# IV9_Christmas.net
KiCad netlist of a schematic drawn in EAGLE
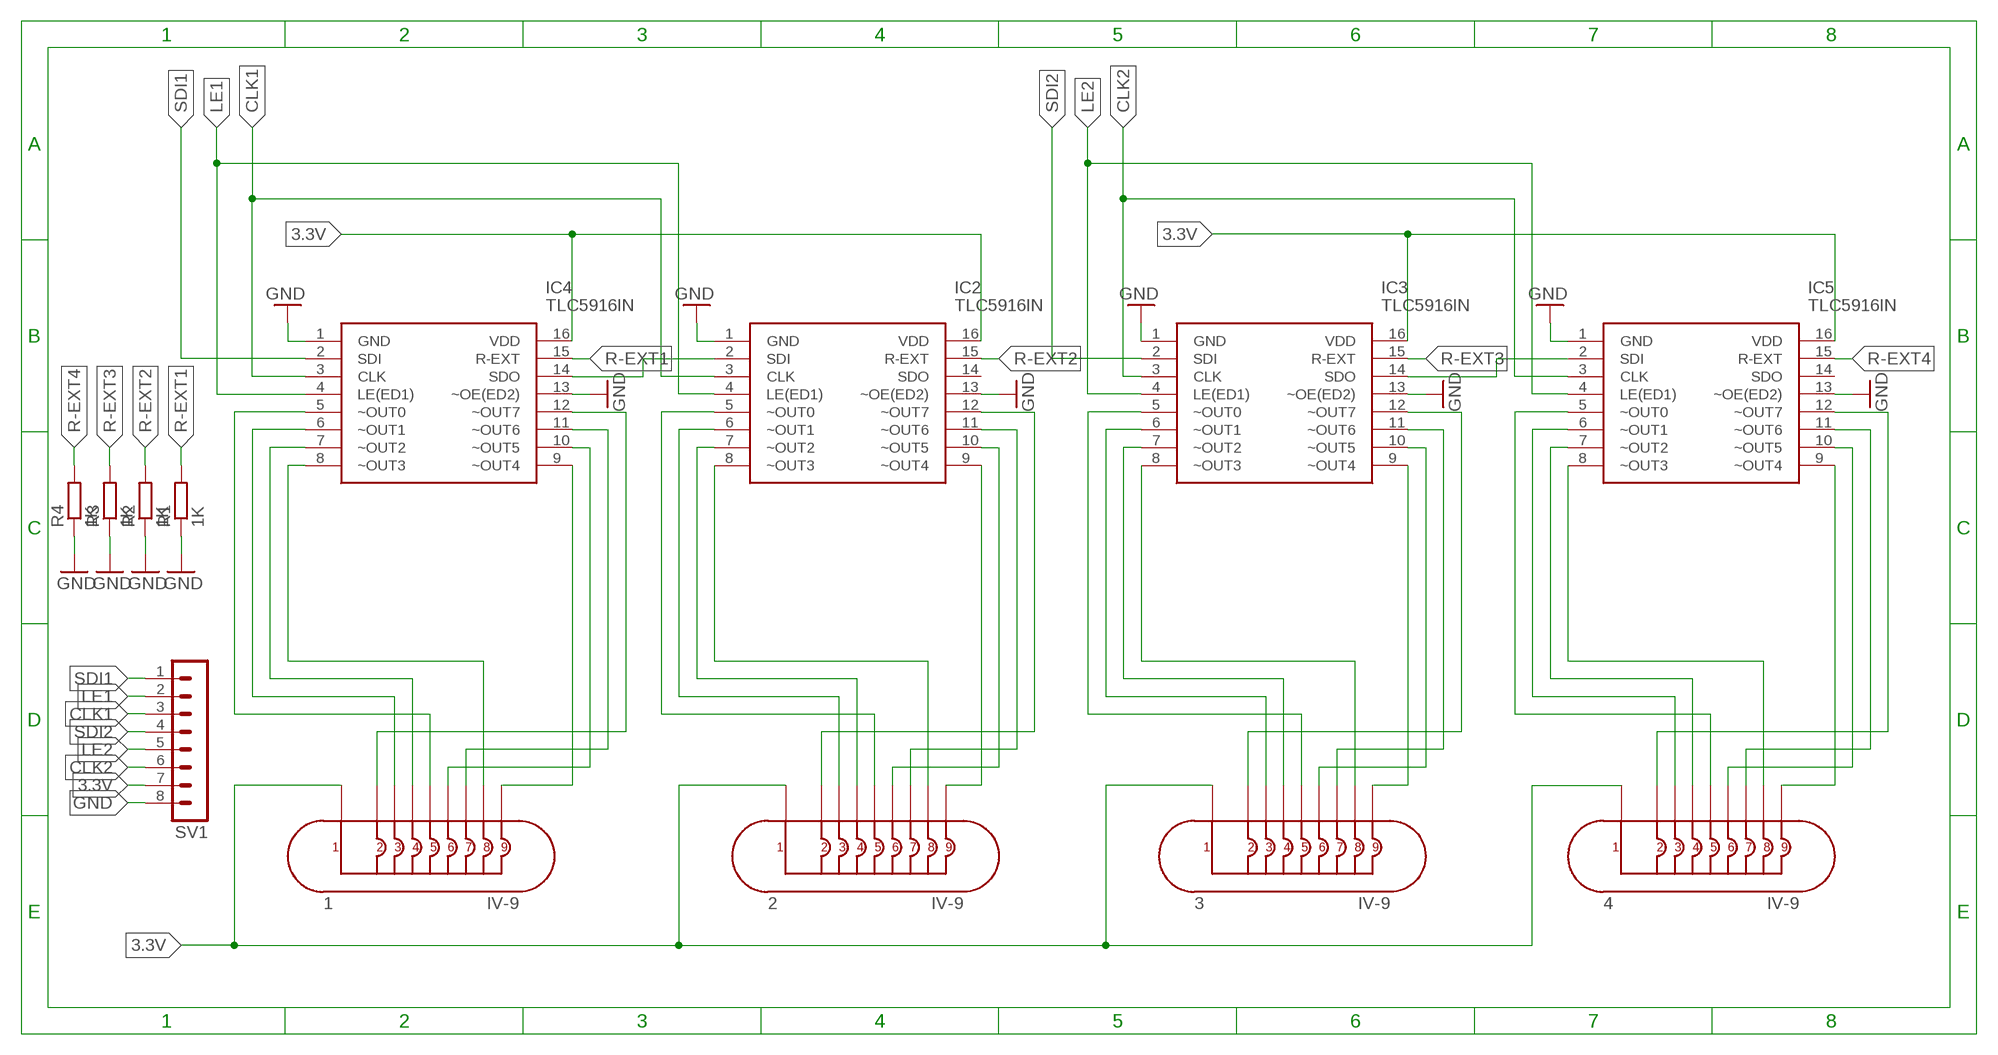
[diagram p0: schematic, sheet 1]
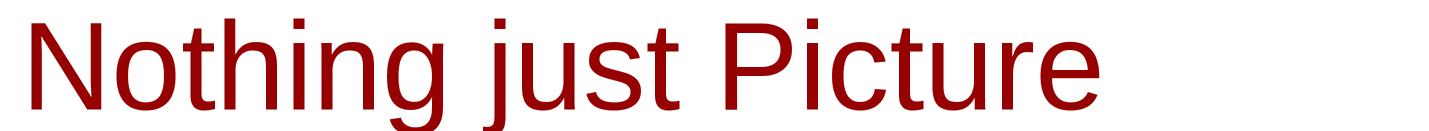
[diagram p1: schematic, sheet 2]

(export (version "E")
  (design (tool "Eeschema 10.0.6"))
  (components
    (comp (ref "1")
      (value "IV-9")
      (footprint "eagle-import:IV-9")
      (libsource (lib "eagle-import") (part "IV-9"))
    )
    (comp (ref "2")
      (value "IV-9")
      (footprint "eagle-import:IV-9")
      (libsource (lib "eagle-import") (part "IV-9"))
    )
    (comp (ref "3")
      (value "IV-9")
      (footprint "eagle-import:IV-9")
      (libsource (lib "eagle-import") (part "IV-9"))
    )
    (comp (ref "4")
      (value "IV-9")
      (footprint "eagle-import:IV-9")
      (libsource (lib "eagle-import") (part "IV-9"))
    )
    (comp (ref "IC2")
      (value "TLC5916IN")
      (footprint "eagle-import:DIP254P762X508-16")
      (fields (field (name "MOUSER_PART_NUMBER") "595-TLC5916IN"))
      (libsource (lib "eagle-import") (part "TLC5916IN"))
    )
    (comp (ref "IC3")
      (value "TLC5916IN")
      (footprint "eagle-import:DIP254P762X508-16")
      (fields (field (name "MOUSER_PART_NUMBER") "595-TLC5916IN"))
      (libsource (lib "eagle-import") (part "TLC5916IN"))
    )
    (comp (ref "IC4")
      (value "TLC5916IN")
      (footprint "eagle-import:DIP254P762X508-16")
      (fields (field (name "MOUSER_PART_NUMBER") "595-TLC5916IN"))
      (libsource (lib "eagle-import") (part "TLC5916IN"))
    )
    (comp (ref "IC5")
      (value "TLC5916IN")
      (footprint "eagle-import:DIP254P762X508-16")
      (fields (field (name "MOUSER_PART_NUMBER") "595-TLC5916IN"))
      (libsource (lib "eagle-import") (part "TLC5916IN"))
    )
    (comp (ref "R1")
      (value "1K")
      (footprint "eagle-import:R1206")
      (libsource (lib "eagle-import") (part "R-EU_R1206"))
    )
    (comp (ref "R2")
      (value "1K")
      (footprint "eagle-import:R1206")
      (libsource (lib "eagle-import") (part "R-EU_R1206"))
    )
    (comp (ref "R3")
      (value "1K")
      (footprint "eagle-import:R1206")
      (libsource (lib "eagle-import") (part "R-EU_R1206"))
    )
    (comp (ref "R4")
      (value "1K")
      (footprint "eagle-import:R1206")
      (libsource (lib "eagle-import") (part "R-EU_R1206"))
    )
    (comp (ref "SV1")
      (value "MA08-1")
      (footprint "eagle-import:MA08-1")
      (libsource (lib "eagle-import") (part "MA08-1"))
    )
  )
  (nets
    (net (code "1") (name "3.3V") (class "Default")
      (node (ref "1") (pin "1") (pinfunction "1_1") (pintype "bidirectional"))
      (node (ref "2") (pin "1") (pinfunction "1_1") (pintype "bidirectional"))
      (node (ref "3") (pin "1") (pinfunction "1_1") (pintype "bidirectional"))
      (node (ref "4") (pin "1") (pinfunction "1_1") (pintype "bidirectional"))
      (node (ref "IC2") (pin "16") (pinfunction "VDD_16") (pintype "bidirectional"))
      (node (ref "IC3") (pin "16") (pinfunction "VDD_16") (pintype "bidirectional"))
      (node (ref "IC4") (pin "16") (pinfunction "VDD_16") (pintype "bidirectional"))
      (node (ref "IC5") (pin "16") (pinfunction "VDD_16") (pintype "bidirectional"))
      (node (ref "SV1") (pin "7") (pinfunction "7_7") (pintype "passive"))
    )
    (net (code "2") (name "CLK1") (class "Default")
      (node (ref "IC2") (pin "3") (pinfunction "CLK_3") (pintype "bidirectional"))
      (node (ref "IC4") (pin "3") (pinfunction "CLK_3") (pintype "bidirectional"))
      (node (ref "SV1") (pin "3") (pinfunction "3_3") (pintype "passive"))
    )
    (net (code "3") (name "CLK2") (class "Default")
      (node (ref "IC3") (pin "3") (pinfunction "CLK_3") (pintype "bidirectional"))
      (node (ref "IC5") (pin "3") (pinfunction "CLK_3") (pintype "bidirectional"))
      (node (ref "SV1") (pin "6") (pinfunction "6_6") (pintype "passive"))
    )
    (net (code "4") (name "GND") (class "Default")
      (node (ref "IC2") (pin "1") (pinfunction "GND_1") (pintype "bidirectional"))
      (node (ref "IC2") (pin "13") (pinfunction "~{OE(ED2})_13") (pintype "bidirectional"))
      (node (ref "IC3") (pin "1") (pinfunction "GND_1") (pintype "bidirectional"))
      (node (ref "IC3") (pin "13") (pinfunction "~{OE(ED2})_13") (pintype "bidirectional"))
      (node (ref "IC4") (pin "1") (pinfunction "GND_1") (pintype "bidirectional"))
      (node (ref "IC4") (pin "13") (pinfunction "~{OE(ED2})_13") (pintype "bidirectional"))
      (node (ref "IC5") (pin "1") (pinfunction "GND_1") (pintype "bidirectional"))
      (node (ref "IC5") (pin "13") (pinfunction "~{OE(ED2})_13") (pintype "bidirectional"))
      (node (ref "R1") (pin "1") (pinfunction "1_1") (pintype "passive"))
      (node (ref "R2") (pin "1") (pinfunction "1_1") (pintype "passive"))
      (node (ref "R3") (pin "1") (pinfunction "1_1") (pintype "passive"))
      (node (ref "R4") (pin "1") (pinfunction "1_1") (pintype "passive"))
      (node (ref "SV1") (pin "8") (pinfunction "8_8") (pintype "passive"))
    )
    (net (code "5") (name "LE1") (class "Default")
      (node (ref "IC2") (pin "4") (pinfunction "LE(ED1)_4") (pintype "bidirectional"))
      (node (ref "IC4") (pin "4") (pinfunction "LE(ED1)_4") (pintype "bidirectional"))
      (node (ref "SV1") (pin "2") (pinfunction "2_2") (pintype "passive"))
    )
    (net (code "6") (name "LE2") (class "Default")
      (node (ref "IC3") (pin "4") (pinfunction "LE(ED1)_4") (pintype "bidirectional"))
      (node (ref "IC5") (pin "4") (pinfunction "LE(ED1)_4") (pintype "bidirectional"))
      (node (ref "SV1") (pin "5") (pinfunction "5_5") (pintype "passive"))
    )
    (net (code "7") (name "Net-(IC2-SDI)") (class "Default")
      (node (ref "IC2") (pin "2") (pinfunction "SDI_2") (pintype "bidirectional"))
      (node (ref "IC4") (pin "14") (pinfunction "SDO_14") (pintype "bidirectional"))
    )
    (net (code "8") (name "Net-(IC2-~{OUT0})") (class "Default")
      (node (ref "2") (pin "5") (pinfunction "5_5") (pintype "bidirectional"))
      (node (ref "IC2") (pin "5") (pinfunction "~{OUT0}_5") (pintype "bidirectional"))
    )
    (net (code "9") (name "Net-(IC2-~{OUT1})") (class "Default")
      (node (ref "2") (pin "3") (pinfunction "3_3") (pintype "bidirectional"))
      (node (ref "IC2") (pin "6") (pinfunction "~{OUT1}_6") (pintype "bidirectional"))
    )
    (net (code "10") (name "Net-(IC2-~{OUT2})") (class "Default")
      (node (ref "2") (pin "4") (pinfunction "4_4") (pintype "bidirectional"))
      (node (ref "IC2") (pin "7") (pinfunction "~{OUT2}_7") (pintype "bidirectional"))
    )
    (net (code "11") (name "Net-(IC2-~{OUT3})") (class "Default")
      (node (ref "2") (pin "8") (pinfunction "8_8") (pintype "bidirectional"))
      (node (ref "IC2") (pin "8") (pinfunction "~{OUT3}_8") (pintype "bidirectional"))
    )
    (net (code "12") (name "Net-(IC2-~{OUT4})") (class "Default")
      (node (ref "2") (pin "9") (pinfunction "9_9") (pintype "bidirectional"))
      (node (ref "IC2") (pin "9") (pinfunction "~{OUT4}_9") (pintype "bidirectional"))
    )
    (net (code "13") (name "Net-(IC2-~{OUT5})") (class "Default")
      (node (ref "2") (pin "6") (pinfunction "6_6") (pintype "bidirectional"))
      (node (ref "IC2") (pin "10") (pinfunction "~{OUT5}_10") (pintype "bidirectional"))
    )
    (net (code "14") (name "Net-(IC2-~{OUT6})") (class "Default")
      (node (ref "2") (pin "7") (pinfunction "7_7") (pintype "bidirectional"))
      (node (ref "IC2") (pin "11") (pinfunction "~{OUT6}_11") (pintype "bidirectional"))
    )
    (net (code "15") (name "Net-(IC2-~{OUT7})") (class "Default")
      (node (ref "2") (pin "2") (pinfunction "2_2") (pintype "bidirectional"))
      (node (ref "IC2") (pin "12") (pinfunction "~{OUT7}_12") (pintype "bidirectional"))
    )
    (net (code "16") (name "Net-(IC3-SDO)") (class "Default")
      (node (ref "IC3") (pin "14") (pinfunction "SDO_14") (pintype "bidirectional"))
      (node (ref "IC5") (pin "2") (pinfunction "SDI_2") (pintype "bidirectional"))
    )
    (net (code "17") (name "Net-(IC3-~{OUT0})") (class "Default")
      (node (ref "3") (pin "5") (pinfunction "5_5") (pintype "bidirectional"))
      (node (ref "IC3") (pin "5") (pinfunction "~{OUT0}_5") (pintype "bidirectional"))
    )
    (net (code "18") (name "Net-(IC3-~{OUT1})") (class "Default")
      (node (ref "3") (pin "3") (pinfunction "3_3") (pintype "bidirectional"))
      (node (ref "IC3") (pin "6") (pinfunction "~{OUT1}_6") (pintype "bidirectional"))
    )
    (net (code "19") (name "Net-(IC3-~{OUT2})") (class "Default")
      (node (ref "3") (pin "4") (pinfunction "4_4") (pintype "bidirectional"))
      (node (ref "IC3") (pin "7") (pinfunction "~{OUT2}_7") (pintype "bidirectional"))
    )
    (net (code "20") (name "Net-(IC3-~{OUT3})") (class "Default")
      (node (ref "3") (pin "8") (pinfunction "8_8") (pintype "bidirectional"))
      (node (ref "IC3") (pin "8") (pinfunction "~{OUT3}_8") (pintype "bidirectional"))
    )
    (net (code "21") (name "Net-(IC3-~{OUT4})") (class "Default")
      (node (ref "3") (pin "9") (pinfunction "9_9") (pintype "bidirectional"))
      (node (ref "IC3") (pin "9") (pinfunction "~{OUT4}_9") (pintype "bidirectional"))
    )
    (net (code "22") (name "Net-(IC3-~{OUT5})") (class "Default")
      (node (ref "3") (pin "6") (pinfunction "6_6") (pintype "bidirectional"))
      (node (ref "IC3") (pin "10") (pinfunction "~{OUT5}_10") (pintype "bidirectional"))
    )
    (net (code "23") (name "Net-(IC3-~{OUT6})") (class "Default")
      (node (ref "3") (pin "7") (pinfunction "7_7") (pintype "bidirectional"))
      (node (ref "IC3") (pin "11") (pinfunction "~{OUT6}_11") (pintype "bidirectional"))
    )
    (net (code "24") (name "Net-(IC3-~{OUT7})") (class "Default")
      (node (ref "3") (pin "2") (pinfunction "2_2") (pintype "bidirectional"))
      (node (ref "IC3") (pin "12") (pinfunction "~{OUT7}_12") (pintype "bidirectional"))
    )
    (net (code "25") (name "Net-(IC4-~{OUT0})") (class "Default")
      (node (ref "1") (pin "5") (pinfunction "5_5") (pintype "bidirectional"))
      (node (ref "IC4") (pin "5") (pinfunction "~{OUT0}_5") (pintype "bidirectional"))
    )
    (net (code "26") (name "Net-(IC4-~{OUT1})") (class "Default")
      (node (ref "1") (pin "3") (pinfunction "3_3") (pintype "bidirectional"))
      (node (ref "IC4") (pin "6") (pinfunction "~{OUT1}_6") (pintype "bidirectional"))
    )
    (net (code "27") (name "Net-(IC4-~{OUT2})") (class "Default")
      (node (ref "1") (pin "4") (pinfunction "4_4") (pintype "bidirectional"))
      (node (ref "IC4") (pin "7") (pinfunction "~{OUT2}_7") (pintype "bidirectional"))
    )
    (net (code "28") (name "Net-(IC4-~{OUT3})") (class "Default")
      (node (ref "1") (pin "8") (pinfunction "8_8") (pintype "bidirectional"))
      (node (ref "IC4") (pin "8") (pinfunction "~{OUT3}_8") (pintype "bidirectional"))
    )
    (net (code "29") (name "Net-(IC4-~{OUT4})") (class "Default")
      (node (ref "1") (pin "9") (pinfunction "9_9") (pintype "bidirectional"))
      (node (ref "IC4") (pin "9") (pinfunction "~{OUT4}_9") (pintype "bidirectional"))
    )
    (net (code "30") (name "Net-(IC4-~{OUT5})") (class "Default")
      (node (ref "1") (pin "6") (pinfunction "6_6") (pintype "bidirectional"))
      (node (ref "IC4") (pin "10") (pinfunction "~{OUT5}_10") (pintype "bidirectional"))
    )
    (net (code "31") (name "Net-(IC4-~{OUT6})") (class "Default")
      (node (ref "1") (pin "7") (pinfunction "7_7") (pintype "bidirectional"))
      (node (ref "IC4") (pin "11") (pinfunction "~{OUT6}_11") (pintype "bidirectional"))
    )
    (net (code "32") (name "Net-(IC4-~{OUT7})") (class "Default")
      (node (ref "1") (pin "2") (pinfunction "2_2") (pintype "bidirectional"))
      (node (ref "IC4") (pin "12") (pinfunction "~{OUT7}_12") (pintype "bidirectional"))
    )
    (net (code "33") (name "Net-(IC5-~{OUT0})") (class "Default")
      (node (ref "4") (pin "5") (pinfunction "5_5") (pintype "bidirectional"))
      (node (ref "IC5") (pin "5") (pinfunction "~{OUT0}_5") (pintype "bidirectional"))
    )
    (net (code "34") (name "Net-(IC5-~{OUT1})") (class "Default")
      (node (ref "4") (pin "3") (pinfunction "3_3") (pintype "bidirectional"))
      (node (ref "IC5") (pin "6") (pinfunction "~{OUT1}_6") (pintype "bidirectional"))
    )
    (net (code "35") (name "Net-(IC5-~{OUT2})") (class "Default")
      (node (ref "4") (pin "4") (pinfunction "4_4") (pintype "bidirectional"))
      (node (ref "IC5") (pin "7") (pinfunction "~{OUT2}_7") (pintype "bidirectional"))
    )
    (net (code "36") (name "Net-(IC5-~{OUT3})") (class "Default")
      (node (ref "4") (pin "8") (pinfunction "8_8") (pintype "bidirectional"))
      (node (ref "IC5") (pin "8") (pinfunction "~{OUT3}_8") (pintype "bidirectional"))
    )
    (net (code "37") (name "Net-(IC5-~{OUT4})") (class "Default")
      (node (ref "4") (pin "9") (pinfunction "9_9") (pintype "bidirectional"))
      (node (ref "IC5") (pin "9") (pinfunction "~{OUT4}_9") (pintype "bidirectional"))
    )
    (net (code "38") (name "Net-(IC5-~{OUT5})") (class "Default")
      (node (ref "4") (pin "6") (pinfunction "6_6") (pintype "bidirectional"))
      (node (ref "IC5") (pin "10") (pinfunction "~{OUT5}_10") (pintype "bidirectional"))
    )
    (net (code "39") (name "Net-(IC5-~{OUT6})") (class "Default")
      (node (ref "4") (pin "7") (pinfunction "7_7") (pintype "bidirectional"))
      (node (ref "IC5") (pin "11") (pinfunction "~{OUT6}_11") (pintype "bidirectional"))
    )
    (net (code "40") (name "Net-(IC5-~{OUT7})") (class "Default")
      (node (ref "4") (pin "2") (pinfunction "2_2") (pintype "bidirectional"))
      (node (ref "IC5") (pin "12") (pinfunction "~{OUT7}_12") (pintype "bidirectional"))
    )
    (net (code "41") (name "R-EXT1") (class "Default")
      (node (ref "IC4") (pin "15") (pinfunction "R-EXT_15") (pintype "bidirectional"))
      (node (ref "R1") (pin "2") (pinfunction "2_2") (pintype "passive"))
    )
    (net (code "42") (name "R-EXT2") (class "Default")
      (node (ref "IC2") (pin "15") (pinfunction "R-EXT_15") (pintype "bidirectional"))
      (node (ref "R2") (pin "2") (pinfunction "2_2") (pintype "passive"))
    )
    (net (code "43") (name "R-EXT3") (class "Default")
      (node (ref "IC3") (pin "15") (pinfunction "R-EXT_15") (pintype "bidirectional"))
      (node (ref "R3") (pin "2") (pinfunction "2_2") (pintype "passive"))
    )
    (net (code "44") (name "R-EXT4") (class "Default")
      (node (ref "IC5") (pin "15") (pinfunction "R-EXT_15") (pintype "bidirectional"))
      (node (ref "R4") (pin "2") (pinfunction "2_2") (pintype "passive"))
    )
    (net (code "45") (name "SDI1") (class "Default")
      (node (ref "IC4") (pin "2") (pinfunction "SDI_2") (pintype "bidirectional"))
      (node (ref "SV1") (pin "1") (pinfunction "1_1") (pintype "passive"))
    )
    (net (code "46") (name "SDI2") (class "Default")
      (node (ref "IC3") (pin "2") (pinfunction "SDI_2") (pintype "bidirectional"))
      (node (ref "SV1") (pin "4") (pinfunction "4_4") (pintype "passive"))
    )
    (net (code "47") (name "unconnected-(IC2-SDO-Pad14)") (class "Default")
      (node (ref "IC2") (pin "14") (pinfunction "SDO_14") (pintype "bidirectional"))
    )
    (net (code "48") (name "unconnected-(IC5-SDO-Pad14)") (class "Default")
      (node (ref "IC5") (pin "14") (pinfunction "SDO_14") (pintype "bidirectional"))
    )
  )
)
